# shoff_900_T24-12.net
KiCad netlist of a schematic drawn in EAGLE
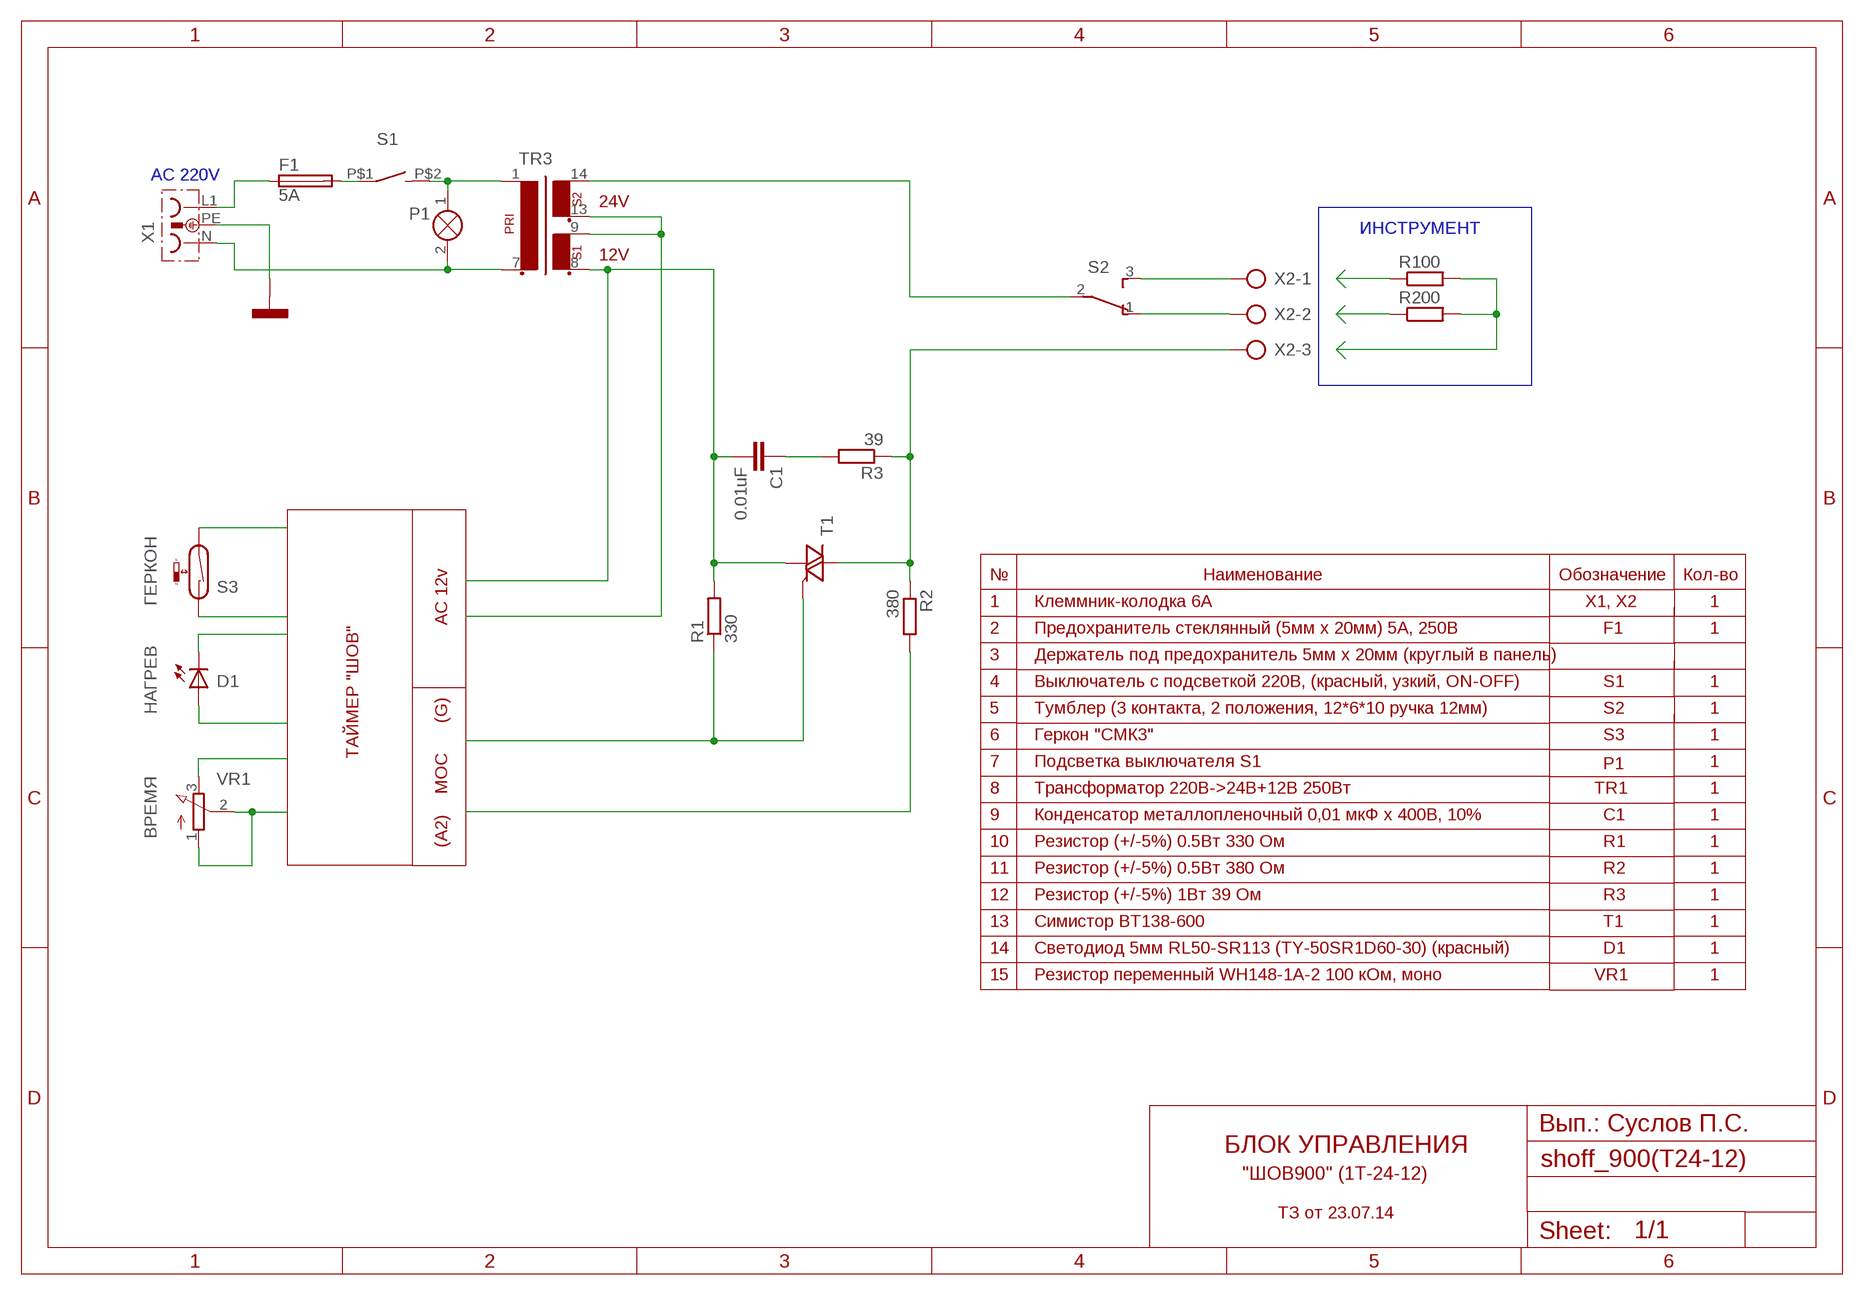
[diagram p0: schematic, sheet 1]

(export (version "E")
  (design (tool "Eeschema 10.0.6"))
  (components
    (comp (ref "C1")
      (value "0.01uF")
      (footprint "eagle-import:C025-030X050")
      (libsource (lib "eagle-import") (part "C-EU025-030X050"))
    )
    (comp (ref "F1")
      (value "5A")
      (footprint "eagle-import:GSH15")
      (fields (field (name "MPN") "64900001039"))
      (libsource (lib "eagle-import") (part "GSH15"))
    )
    (comp (ref "GG")
      (value "MASSE_ALLGEMEIN")
      (footprint "eagle-import:MASSE_ALLGEMEIN")
      (libsource (lib "eagle-import") (part "MASSE_ALLGEMEIN"))
    )
    (comp (ref "P1")
      (value "SIGNALLAMPE")
      (footprint "eagle-import:LAMPE")
      (libsource (lib "eagle-import") (part "SIGNALLAMPE"))
    )
    (comp (ref "R1")
      (value "330")
      (footprint "eagle-import:0207_5V")
      (libsource (lib "eagle-import") (part "R-EU_0207/5V"))
    )
    (comp (ref "R2")
      (value "380")
      (footprint "eagle-import:0207_5V")
      (libsource (lib "eagle-import") (part "R-EU_0207/5V"))
    )
    (comp (ref "R3")
      (value "39")
      (footprint "eagle-import:0207_5V")
      (libsource (lib "eagle-import") (part "R-EU_0207/5V"))
    )
    (comp (ref "R100")
      (value "R-EU_R0201")
      (footprint "eagle-import:R0201")
      (libsource (lib "eagle-import") (part "R-EU_R0201"))
    )
    (comp (ref "R200")
      (value "R-EU_R0201")
      (footprint "eagle-import:R0201")
      (libsource (lib "eagle-import") (part "R-EU_R0201"))
    )
    (comp (ref "S1")
      (value "SCHLIESSER_ARBEITSKONTAKT")
      (footprint "eagle-import:1")
      (libsource (lib "eagle-import") (part "SCHLIESSER_ARBEITSKONTAKT"))
    )
    (comp (ref "S2")
      (value "TL36WO")
      (footprint "eagle-import:TL3XWO")
      (libsource (lib "eagle-import") (part "TL36WO"))
    )
    (comp (ref "S3")
      (value "ГЕРКОН")
      (footprint "eagle-import:CT10-G1")
      (fields (field (name "MF") "COTO TECHNOLOGY") (field (name "MPN") "CT10-1530-G1"))
      (libsource (lib "eagle-import") (part "REED-SWITCH-CT10-1530-G1"))
    )
    (comp (ref "T1")
      (value "BTA26-V")
      (footprint "eagle-import:TOP3S-1")
      (libsource (lib "eagle-import") (part "BTA26-V"))
    )
    (comp (ref "TR3")
      (value "BV054-5387.0K")
      (footprint "eagle-import:EI54-18,8_16VA")
      (libsource (lib "eagle-import") (part "BV054-5387.0K"))
    )
    (comp (ref "X1")
      (value "STECKDOSE")
      (footprint "eagle-import:STECKDOSE")
      (libsource (lib "eagle-import") (part "STECKDOSE"))
    )
    (comp (ref "X2")
      (value "AK500/3")
      (footprint "eagle-import:AK500_3")
      (libsource (lib "eagle-import") (part "AK500/3"))
    )
    (comp (ref "ВРЕМЯ")
      (value "3RP/1610N")
      (footprint "eagle-import:3RP_1610N")
      (libsource (lib "eagle-import") (part "3RP/1610N"))
    )
    (comp (ref "ГОТОВ")
      (value "НАГРЕВ")
      (footprint "eagle-import:LED5MM")
      (libsource (lib "eagle-import") (part "LED5MM"))
    )
  )
  (nets
    (net (code "1") (name "Net-(C1-Pad1)") (class "Default")
      (node (ref "C1") (pin "1") (pinfunction "1_1") (pintype "passive"))
      (node (ref "R3") (pin "2") (pinfunction "2_2") (pintype "passive"))
    )
    (net (code "2") (name "Net-(F1-Pad1)") (class "Default")
      (node (ref "F1") (pin "1") (pinfunction "1_1") (pintype "passive"))
      (node (ref "X1") (pin "L1") (pinfunction "L1_L1") (pintype "passive"))
    )
    (net (code "3") (name "Net-(GG-0V)") (class "Default")
      (node (ref "GG") (pin "1") (pinfunction "0V_1") (pintype "passive"))
      (node (ref "X1") (pin "PE") (pinfunction "PE_PE") (pintype "passive"))
    )
    (net (code "4") (name "Net-(P1-X1)") (class "Default")
      (node (ref "P1") (pin "1") (pinfunction "X1_1") (pintype "passive"))
      (node (ref "S1") (pin "P$2") (pinfunction "3_P$2") (pintype "passive"))
      (node (ref "TR3") (pin "1") (pinfunction "1_1") (pintype "passive"))
    )
    (net (code "5") (name "Net-(P1-X2)") (class "Default")
      (node (ref "P1") (pin "2") (pinfunction "X2_2") (pintype "passive"))
      (node (ref "TR3") (pin "7") (pinfunction "2_7") (pintype "passive"))
      (node (ref "X1") (pin "N") (pinfunction "N_N") (pintype "passive"))
    )
    (net (code "6") (name "Net-(R1-Pad1)") (class "Default")
      (node (ref "R1") (pin "1") (pinfunction "1_1") (pintype "passive"))
      (node (ref "T1") (pin "G") (pinfunction "G_G") (pintype "passive"))
    )
    (net (code "7") (name "Net-(R100-Pad2)") (class "Default")
      (node (ref "R100") (pin "2") (pinfunction "2_2") (pintype "passive"))
      (node (ref "R200") (pin "2") (pinfunction "2_2") (pintype "passive"))
    )
    (net (code "8") (name "Net-(S1-4)") (class "Default")
      (node (ref "F1") (pin "2") (pinfunction "2_2") (pintype "passive"))
      (node (ref "S1") (pin "P$1") (pinfunction "4_P$1") (pintype "passive"))
    )
    (net (code "9") (name "Net-(S2-O)") (class "Default")
      (node (ref "S2") (pin "1") (pinfunction "O_1") (pintype "passive"))
      (node (ref "X2") (pin "2") (pinfunction "KL_2") (pintype "passive"))
    )
    (net (code "10") (name "Net-(S2-P)") (class "Default")
      (node (ref "S2") (pin "2") (pinfunction "P_2") (pintype "passive"))
      (node (ref "TR3") (pin "14") (pinfunction "6_14") (pintype "passive"))
    )
    (net (code "11") (name "Net-(S2-S)") (class "Default")
      (node (ref "S2") (pin "3") (pinfunction "S_3") (pintype "passive"))
      (node (ref "X2") (pin "1") (pinfunction "KL_1") (pintype "passive"))
    )
    (net (code "12") (name "Net-(TR3-3)") (class "Default")
      (node (ref "C1") (pin "2") (pinfunction "2_2") (pintype "passive"))
      (node (ref "R1") (pin "2") (pinfunction "2_2") (pintype "passive"))
      (node (ref "T1") (pin "A1") (pinfunction "A1_A1") (pintype "passive"))
      (node (ref "TR3") (pin "8") (pinfunction "3_8") (pintype "passive"))
    )
    (net (code "13") (name "Net-(TR3-4)") (class "Default")
      (node (ref "TR3") (pin "13") (pinfunction "5_13") (pintype "passive"))
      (node (ref "TR3") (pin "9") (pinfunction "4_9") (pintype "passive"))
    )
    (net (code "14") (name "Net-(X2C-KL)") (class "Default")
      (node (ref "R2") (pin "1") (pinfunction "1_1") (pintype "passive"))
      (node (ref "R3") (pin "1") (pinfunction "1_1") (pintype "passive"))
      (node (ref "T1") (pin "A2") (pinfunction "A2_A2") (pintype "passive"))
      (node (ref "X2") (pin "3") (pinfunction "KL_3") (pintype "passive"))
    )
    (net (code "15") (name "Net-(ВРЕМЯ-A)") (class "Default")
      (node (ref "ВРЕМЯ") (pin "1") (pinfunction "A_1") (pintype "passive"))
      (node (ref "ВРЕМЯ") (pin "2") (pinfunction "S_2") (pintype "passive"))
    )
    (net (code "16") (name "unconnected-(R2-Pad2)") (class "Default")
      (node (ref "R2") (pin "2") (pinfunction "2_2") (pintype "passive"))
    )
    (net (code "17") (name "unconnected-(R100-Pad1)") (class "Default")
      (node (ref "R100") (pin "1") (pinfunction "1_1") (pintype "passive"))
    )
    (net (code "18") (name "unconnected-(R200-Pad1)") (class "Default")
      (node (ref "R200") (pin "1") (pinfunction "1_1") (pintype "passive"))
    )
    (net (code "19") (name "unconnected-(S3-Pad1)") (class "Default")
      (node (ref "S3") (pin "1") (pinfunction "1_1") (pintype "passive"))
    )
    (net (code "20") (name "unconnected-(S3-Pad2)") (class "Default")
      (node (ref "S3") (pin "2") (pinfunction "2_2") (pintype "passive"))
    )
    (net (code "21") (name "unconnected-(ВРЕМЯ-E-Pad3)") (class "Default")
      (node (ref "ВРЕМЯ") (pin "3") (pinfunction "E_3") (pintype "passive"))
    )
    (net (code "22") (name "unconnected-(ГОТОВ-C-PadK)") (class "Default")
      (node (ref "ГОТОВ") (pin "K") (pinfunction "C_K") (pintype "passive"))
    )
    (net (code "23") (name "unconnected-(ГОТОВ-PadA)") (class "Default")
      (node (ref "ГОТОВ") (pin "A") (pinfunction "A_A") (pintype "passive"))
    )
  )
)
